# Raspberry_Pi.net
KiCad netlist of a schematic drawn in Altium Designer
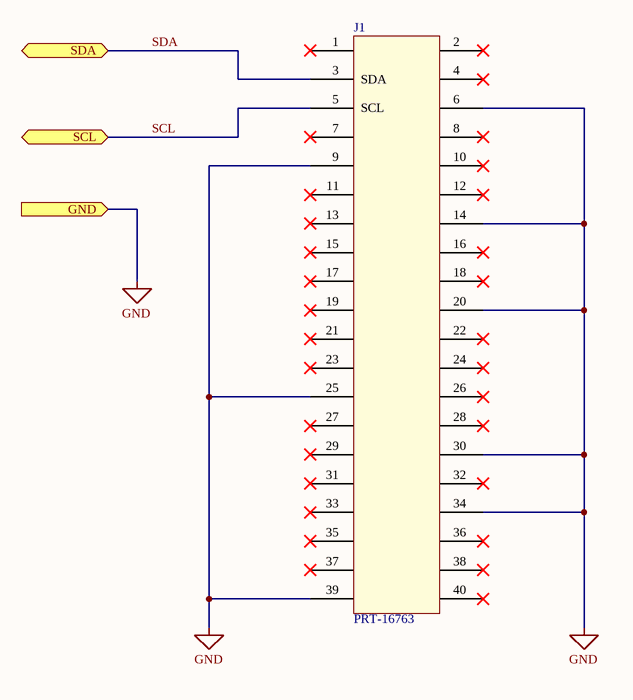
[diagram p0: Raspberry Pi.SchDoc]

(export (version "E")
  (design (tool "Eeschema 10.0.6"))
  (components
    (comp (ref "J1")
      (value "PRT-16763")
      (footprint "FP-SFH11-PBPC-D20-ST-BK-MFG")
      (description "Headers & Wire Housings Extended GPIO Female Header - 2x20 Pin (16mm/7.30mm)")
      (libsource (lib "Callisto Control Board") (part "Raspberry Pi 3+ Header"))
    )
  )
  (nets
    (net (code "1") (name "/SCL") (class "Default")
      (node (ref "J1") (pin "5") (pinfunction "SCL_5") (pintype "passive"))
    )
    (net (code "2") (name "/SDA") (class "Default")
      (node (ref "J1") (pin "3") (pinfunction "SDA_3") (pintype "passive"))
    )
    (net (code "3") (name "GND") (class "Default")
      (node (ref "J1") (pin "14") (pinfunction "14_14") (pintype "passive"))
      (node (ref "J1") (pin "20") (pinfunction "20_20") (pintype "passive"))
      (node (ref "J1") (pin "25") (pinfunction "25_25") (pintype "passive"))
      (node (ref "J1") (pin "30") (pinfunction "30_30") (pintype "passive"))
      (node (ref "J1") (pin "34") (pinfunction "34_34") (pintype "passive"))
      (node (ref "J1") (pin "39") (pinfunction "39_39") (pintype "passive"))
      (node (ref "J1") (pin "6") (pinfunction "6_6") (pintype "passive"))
      (node (ref "J1") (pin "9") (pinfunction "9_9") (pintype "passive"))
    )
    (net (code "4") (name "unconnected-(J1-Pad1)") (class "Default")
      (node (ref "J1") (pin "1") (pintype "passive+no_connect"))
    )
    (net (code "5") (name "unconnected-(J1-Pad2)") (class "Default")
      (node (ref "J1") (pin "2") (pintype "passive+no_connect"))
    )
    (net (code "6") (name "unconnected-(J1-Pad4)") (class "Default")
      (node (ref "J1") (pin "4") (pintype "passive+no_connect"))
    )
    (net (code "7") (name "unconnected-(J1-Pad7)") (class "Default")
      (node (ref "J1") (pin "7") (pinfunction "7_7") (pintype "passive+no_connect"))
    )
    (net (code "8") (name "unconnected-(J1-Pad8)") (class "Default")
      (node (ref "J1") (pin "8") (pinfunction "8_8") (pintype "passive+no_connect"))
    )
    (net (code "9") (name "unconnected-(J1-Pad10)") (class "Default")
      (node (ref "J1") (pin "10") (pinfunction "10_10") (pintype "passive+no_connect"))
    )
    (net (code "10") (name "unconnected-(J1-Pad11)") (class "Default")
      (node (ref "J1") (pin "11") (pinfunction "11_11") (pintype "passive+no_connect"))
    )
    (net (code "11") (name "unconnected-(J1-Pad12)") (class "Default")
      (node (ref "J1") (pin "12") (pinfunction "12_12") (pintype "passive+no_connect"))
    )
    (net (code "12") (name "unconnected-(J1-Pad13)") (class "Default")
      (node (ref "J1") (pin "13") (pinfunction "13_13") (pintype "passive+no_connect"))
    )
    (net (code "13") (name "unconnected-(J1-Pad15)") (class "Default")
      (node (ref "J1") (pin "15") (pinfunction "15_15") (pintype "passive+no_connect"))
    )
    (net (code "14") (name "unconnected-(J1-Pad16)") (class "Default")
      (node (ref "J1") (pin "16") (pinfunction "16_16") (pintype "passive+no_connect"))
    )
    (net (code "15") (name "unconnected-(J1-Pad17)") (class "Default")
      (node (ref "J1") (pin "17") (pinfunction "17_17") (pintype "passive+no_connect"))
    )
    (net (code "16") (name "unconnected-(J1-Pad18)") (class "Default")
      (node (ref "J1") (pin "18") (pinfunction "18_18") (pintype "passive+no_connect"))
    )
    (net (code "17") (name "unconnected-(J1-Pad19)") (class "Default")
      (node (ref "J1") (pin "19") (pinfunction "19_19") (pintype "passive+no_connect"))
    )
    (net (code "18") (name "unconnected-(J1-Pad21)") (class "Default")
      (node (ref "J1") (pin "21") (pinfunction "21_21") (pintype "passive+no_connect"))
    )
    (net (code "19") (name "unconnected-(J1-Pad22)") (class "Default")
      (node (ref "J1") (pin "22") (pinfunction "22_22") (pintype "passive+no_connect"))
    )
    (net (code "20") (name "unconnected-(J1-Pad23)") (class "Default")
      (node (ref "J1") (pin "23") (pinfunction "23_23") (pintype "passive+no_connect"))
    )
    (net (code "21") (name "unconnected-(J1-Pad24)") (class "Default")
      (node (ref "J1") (pin "24") (pinfunction "24_24") (pintype "passive+no_connect"))
    )
    (net (code "22") (name "unconnected-(J1-Pad26)") (class "Default")
      (node (ref "J1") (pin "26") (pinfunction "26_26") (pintype "passive+no_connect"))
    )
    (net (code "23") (name "unconnected-(J1-Pad27)") (class "Default")
      (node (ref "J1") (pin "27") (pinfunction "27_27") (pintype "passive+no_connect"))
    )
    (net (code "24") (name "unconnected-(J1-Pad28)") (class "Default")
      (node (ref "J1") (pin "28") (pinfunction "28_28") (pintype "passive+no_connect"))
    )
    (net (code "25") (name "unconnected-(J1-Pad29)") (class "Default")
      (node (ref "J1") (pin "29") (pinfunction "29_29") (pintype "passive+no_connect"))
    )
    (net (code "26") (name "unconnected-(J1-Pad31)") (class "Default")
      (node (ref "J1") (pin "31") (pinfunction "31_31") (pintype "passive+no_connect"))
    )
    (net (code "27") (name "unconnected-(J1-Pad32)") (class "Default")
      (node (ref "J1") (pin "32") (pinfunction "32_32") (pintype "passive+no_connect"))
    )
    (net (code "28") (name "unconnected-(J1-Pad33)") (class "Default")
      (node (ref "J1") (pin "33") (pinfunction "33_33") (pintype "passive+no_connect"))
    )
    (net (code "29") (name "unconnected-(J1-Pad35)") (class "Default")
      (node (ref "J1") (pin "35") (pinfunction "35_35") (pintype "passive+no_connect"))
    )
    (net (code "30") (name "unconnected-(J1-Pad36)") (class "Default")
      (node (ref "J1") (pin "36") (pinfunction "36_36") (pintype "passive+no_connect"))
    )
    (net (code "31") (name "unconnected-(J1-Pad37)") (class "Default")
      (node (ref "J1") (pin "37") (pinfunction "37_37") (pintype "passive+no_connect"))
    )
    (net (code "32") (name "unconnected-(J1-Pad38)") (class "Default")
      (node (ref "J1") (pin "38") (pinfunction "38_38") (pintype "passive+no_connect"))
    )
    (net (code "33") (name "unconnected-(J1-Pad40)") (class "Default")
      (node (ref "J1") (pin "40") (pinfunction "40_40") (pintype "passive+no_connect"))
    )
  )
)
